# swr-antenna.net
KiCad netlist of a schematic drawn in Altium Designer
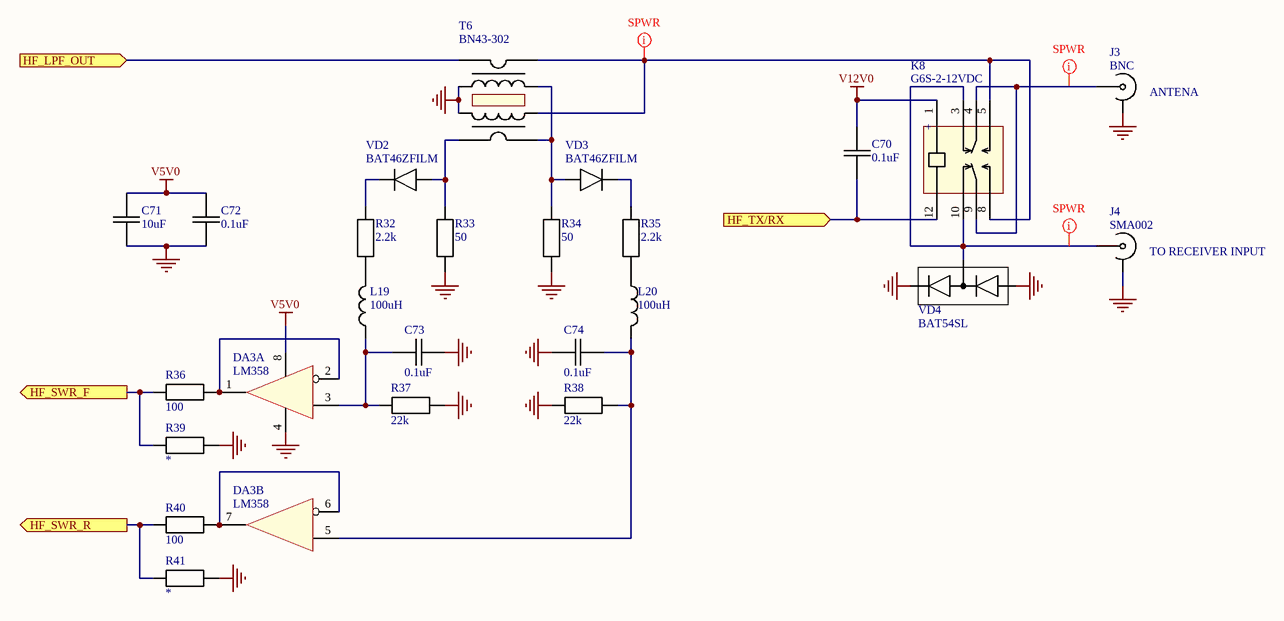
[diagram p0: swr-antenna.SchDoc]

(export (version "E")
  (design (tool "Eeschema 10.0.6"))
  (components
    (comp (ref "C70")
      (value "0.1uF")
      (footprint "CAPC2013X100N")
      (description "Capacitor 2x1.25 mm")
      (libsource (lib "common-lib") (part "Cap0805"))
    )
    (comp (ref "C71")
      (value "10uF")
      (footprint "CAPC2013X100N")
      (description "Capacitor 2x1.25 mm")
      (libsource (lib "common-lib") (part "Cap0805"))
    )
    (comp (ref "C72")
      (value "0.1uF")
      (footprint "CAPC2013X100N")
      (description "Capacitor 2x1.25 mm")
      (libsource (lib "common-lib") (part "Cap0805"))
    )
    (comp (ref "C73")
      (value "0.1uF")
      (footprint "CAPC2013X100N")
      (description "Capacitor 2x1.25 mm")
      (libsource (lib "common-lib") (part "Cap0805"))
    )
    (comp (ref "C74")
      (value "0.1uF")
      (footprint "CAPC2013X100N")
      (description "Capacitor 2x1.25 mm")
      (libsource (lib "common-lib") (part "Cap0805"))
    )
    (comp (ref "DA3")
      (value "LM358")
      (footprint "SOIC127P600X175-8N")
      (description "Single Supply Dual\r\nOperational Amplifiers")
      (libsource (lib "PALib") (part "LM358"))
    )
    (comp (ref "J3")
      (value "BNC")
      (footprint "BNC-TYCO_1-1337542-0")
      (description "EM-BC028M-NGP-50")
      (libsource (lib "PALib") (part "RF Connector"))
    )
    (comp (ref "J4") (value "SMA002") (footprint "SMA002") (libsource (lib "PALib") (part "RF Connector")))
    (comp (ref "K8")
      (value "G6S-2-12VDC")
      (footprint "G6S-2")
      (description "Compact, Industry-Standard 2-pole relay")
      (libsource (lib "PALib") (part "G6S-2-12VDC"))
    )
    (comp (ref "L19")
      (value "100uH")
      (footprint "INDUCTOR-1008")
      (description "SWI1008HT101K-Hitano")
      (libsource (lib "PALib") (part "Inductor"))
    )
    (comp (ref "L20")
      (value "100uH")
      (footprint "INDUCTOR-1008")
      (description "SWI1008HT101K-Hitano")
      (libsource (lib "") (part "Inductor_1"))
    )
    (comp (ref "R32")
      (value "2.2k")
      (footprint "RESC2013X64N")
      (libsource (lib "common-lib") (part "Res0805"))
    )
    (comp (ref "R33") (value "50") (footprint "RESC2013X64N") (libsource (lib "common-lib") (part "Res0805")))
    (comp (ref "R34") (value "50") (footprint "RESC2013X64N") (libsource (lib "common-lib") (part "Res0805")))
    (comp (ref "R35")
      (value "2.2k")
      (footprint "RESC2013X64N")
      (libsource (lib "common-lib") (part "Res0805"))
    )
    (comp (ref "R36")
      (value "100")
      (footprint "RESC2013X64N")
      (libsource (lib "common-lib") (part "Res0805"))
    )
    (comp (ref "R37")
      (value "22k")
      (footprint "RESC2013X64N")
      (libsource (lib "common-lib") (part "Res0805"))
    )
    (comp (ref "R38")
      (value "22k")
      (footprint "RESC2013X64N")
      (libsource (lib "common-lib") (part "Res0805"))
    )
    (comp (ref "R39") (value "*") (footprint "RESC2013X64N") (libsource (lib "common-lib") (part "Res0805")))
    (comp (ref "R40")
      (value "100")
      (footprint "RESC2013X64N")
      (libsource (lib "common-lib") (part "Res0805"))
    )
    (comp (ref "R41") (value "*") (footprint "RESC2013X64N") (libsource (lib "common-lib") (part "Res0805")))
    (comp (ref "T6") (value "BN43-302") (footprint "TANDEM") (libsource (lib "PALib") (part "tandem match")))
    (comp (ref "VD2")
      (value "BAT46ZFILM")
      (footprint "SOD3816X118N")
      (description "Small signal Schottky diodes\r\nimrad")
      (libsource (lib "PALib") (part "DIODE"))
    )
    (comp (ref "VD3")
      (value "BAT46ZFILM")
      (footprint "SOD3816X118N")
      (description "Small signal Schottky diodes\r\nimrad")
      (libsource (lib "PALib") (part "DIODE"))
    )
    (comp (ref "VD4")
      (value "BAT54SL")
      (footprint "SOT95P229X119-3N")
      (libsource (lib "common-lib") (part "DIODE-2-1A-3C-3A-2C"))
    )
  )
  (nets
    (net (code "1") (name "/HF_LPF_OUT") (class "Default") (node (ref "T6") (pin "1") (pintype "passive")))
    (net (code "2") (name "/HF_SWR_F") (class "Default")
      (node (ref "R36") (pin "2") (pintype "passive"))
      (node (ref "R39") (pin "2") (pintype "passive"))
    )
    (net (code "3") (name "/HF_SWR_R") (class "Default")
      (node (ref "R40") (pin "2") (pintype "passive"))
      (node (ref "R41") (pin "2") (pintype "passive"))
    )
    (net (code "4") (name "/HF_TX{slash}RX") (class "Default")
      (node (ref "C70") (pin "1") (pintype "passive"))
      (node (ref "K8") (pin "12") (pintype "passive"))
    )
    (net (code "5") (name "GND") (class "Default")
      (node (ref "C71") (pin "1") (pintype "passive"))
      (node (ref "C72") (pin "1") (pintype "passive"))
      (node (ref "C73") (pin "2") (pintype "passive"))
      (node (ref "C74") (pin "1") (pintype "passive"))
      (node (ref "DA3") (pin "4") (pinfunction "GND_4") (pintype "passive"))
      (node (ref "J3") (pin "2") (pinfunction "GND_2") (pintype "passive"))
      (node (ref "J4") (pin "2") (pinfunction "GND_2") (pintype "passive"))
      (node (ref "R33") (pin "1") (pintype "passive"))
      (node (ref "R34") (pin "1") (pintype "passive"))
      (node (ref "R37") (pin "1") (pintype "passive"))
      (node (ref "R38") (pin "2") (pintype "passive"))
      (node (ref "R39") (pin "1") (pintype "passive"))
      (node (ref "R41") (pin "1") (pintype "passive"))
      (node (ref "T6") (pin "3") (pintype "passive"))
      (node (ref "T6") (pin "5") (pintype "passive"))
      (node (ref "VD4") (pin "1") (pinfunction "A_1") (pintype "passive"))
      (node (ref "VD4") (pin "2") (pinfunction "C_2") (pintype "passive"))
    )
    (net (code "6") (name "Net-(DA3A-IN1+)") (class "Default")
      (node (ref "C73") (pin "1") (pintype "passive"))
      (node (ref "DA3") (pin "3") (pinfunction "IN1+_3") (pintype "passive"))
      (node (ref "L19") (pin "1") (pintype "passive"))
      (node (ref "R37") (pin "2") (pintype "passive"))
    )
    (net (code "7") (name "Net-(DA3A-IN1-)") (class "Default")
      (node (ref "DA3") (pin "1") (pinfunction "OUT1_1") (pintype "passive"))
      (node (ref "DA3") (pin "2") (pinfunction "IN1-_2") (pintype "passive"))
      (node (ref "R36") (pin "1") (pintype "passive"))
    )
    (net (code "8") (name "Net-(DA3B-IN2+)") (class "Default")
      (node (ref "C74") (pin "2") (pintype "passive"))
      (node (ref "DA3") (pin "5") (pinfunction "IN2+_5") (pintype "passive"))
      (node (ref "L20") (pin "2") (pintype "passive"))
      (node (ref "R38") (pin "1") (pintype "passive"))
    )
    (net (code "9") (name "Net-(DA3B-IN2-)") (class "Default")
      (node (ref "DA3") (pin "6") (pinfunction "IN2-_6") (pintype "passive"))
      (node (ref "DA3") (pin "7") (pinfunction "OUT2_7") (pintype "passive"))
      (node (ref "R40") (pin "1") (pintype "passive"))
    )
    (net (code "10") (name "Net-(J3-RF)") (class "Default")
      (node (ref "J3") (pin "1") (pinfunction "RF_1") (pintype "passive"))
      (node (ref "K8") (pin "4") (pintype "passive"))
      (node (ref "K8") (pin "9") (pintype "passive"))
    )
    (net (code "11") (name "Net-(J4-RF)") (class "Default")
      (node (ref "J4") (pin "1") (pinfunction "RF_1") (pintype "passive"))
      (node (ref "K8") (pin "10") (pintype "passive"))
      (node (ref "K8") (pin "3") (pintype "passive"))
      (node (ref "VD4") (pin "3") (pinfunction "AC_3") (pintype "passive"))
    )
    (net (code "12") (name "Net-(K8-Pad5)") (class "Default")
      (node (ref "K8") (pin "5") (pintype "passive"))
      (node (ref "K8") (pin "8") (pintype "passive"))
      (node (ref "T6") (pin "2") (pintype "passive"))
      (node (ref "T6") (pin "6") (pintype "passive"))
    )
    (net (code "13") (name "Net-(L19-Pad2)") (class "Default")
      (node (ref "L19") (pin "2") (pintype "passive"))
      (node (ref "R32") (pin "1") (pintype "passive"))
    )
    (net (code "14") (name "Net-(L20-Pad1)") (class "Default")
      (node (ref "L20") (pin "1") (pintype "passive"))
      (node (ref "R35") (pin "1") (pintype "passive"))
    )
    (net (code "15") (name "Net-(VD2-A)") (class "Default")
      (node (ref "R33") (pin "2") (pintype "passive"))
      (node (ref "T6") (pin "7") (pintype "passive"))
      (node (ref "VD2") (pin "2") (pinfunction "A_2") (pintype "passive"))
    )
    (net (code "16") (name "Net-(VD2-C)") (class "Default")
      (node (ref "R32") (pin "2") (pintype "passive"))
      (node (ref "VD2") (pin "1") (pinfunction "C_1") (pintype "passive"))
    )
    (net (code "17") (name "Net-(VD3-A)") (class "Default")
      (node (ref "R34") (pin "2") (pintype "passive"))
      (node (ref "T6") (pin "4") (pintype "passive"))
      (node (ref "T6") (pin "8") (pintype "passive"))
      (node (ref "VD3") (pin "2") (pinfunction "A_2") (pintype "passive"))
    )
    (net (code "18") (name "Net-(VD3-C)") (class "Default")
      (node (ref "R35") (pin "2") (pintype "passive"))
      (node (ref "VD3") (pin "1") (pinfunction "C_1") (pintype "passive"))
    )
    (net (code "19") (name "V5V0") (class "Default")
      (node (ref "C71") (pin "2") (pintype "passive"))
      (node (ref "C72") (pin "2") (pintype "passive"))
      (node (ref "DA3") (pin "8") (pinfunction "VCC_8") (pintype "passive"))
    )
    (net (code "20") (name "V12V0") (class "Default")
      (node (ref "C70") (pin "2") (pintype "passive"))
      (node (ref "K8") (pin "1") (pintype "passive"))
    )
  )
)
